# ObdBackplane.net
KiCad netlist of a schematic drawn in EAGLE
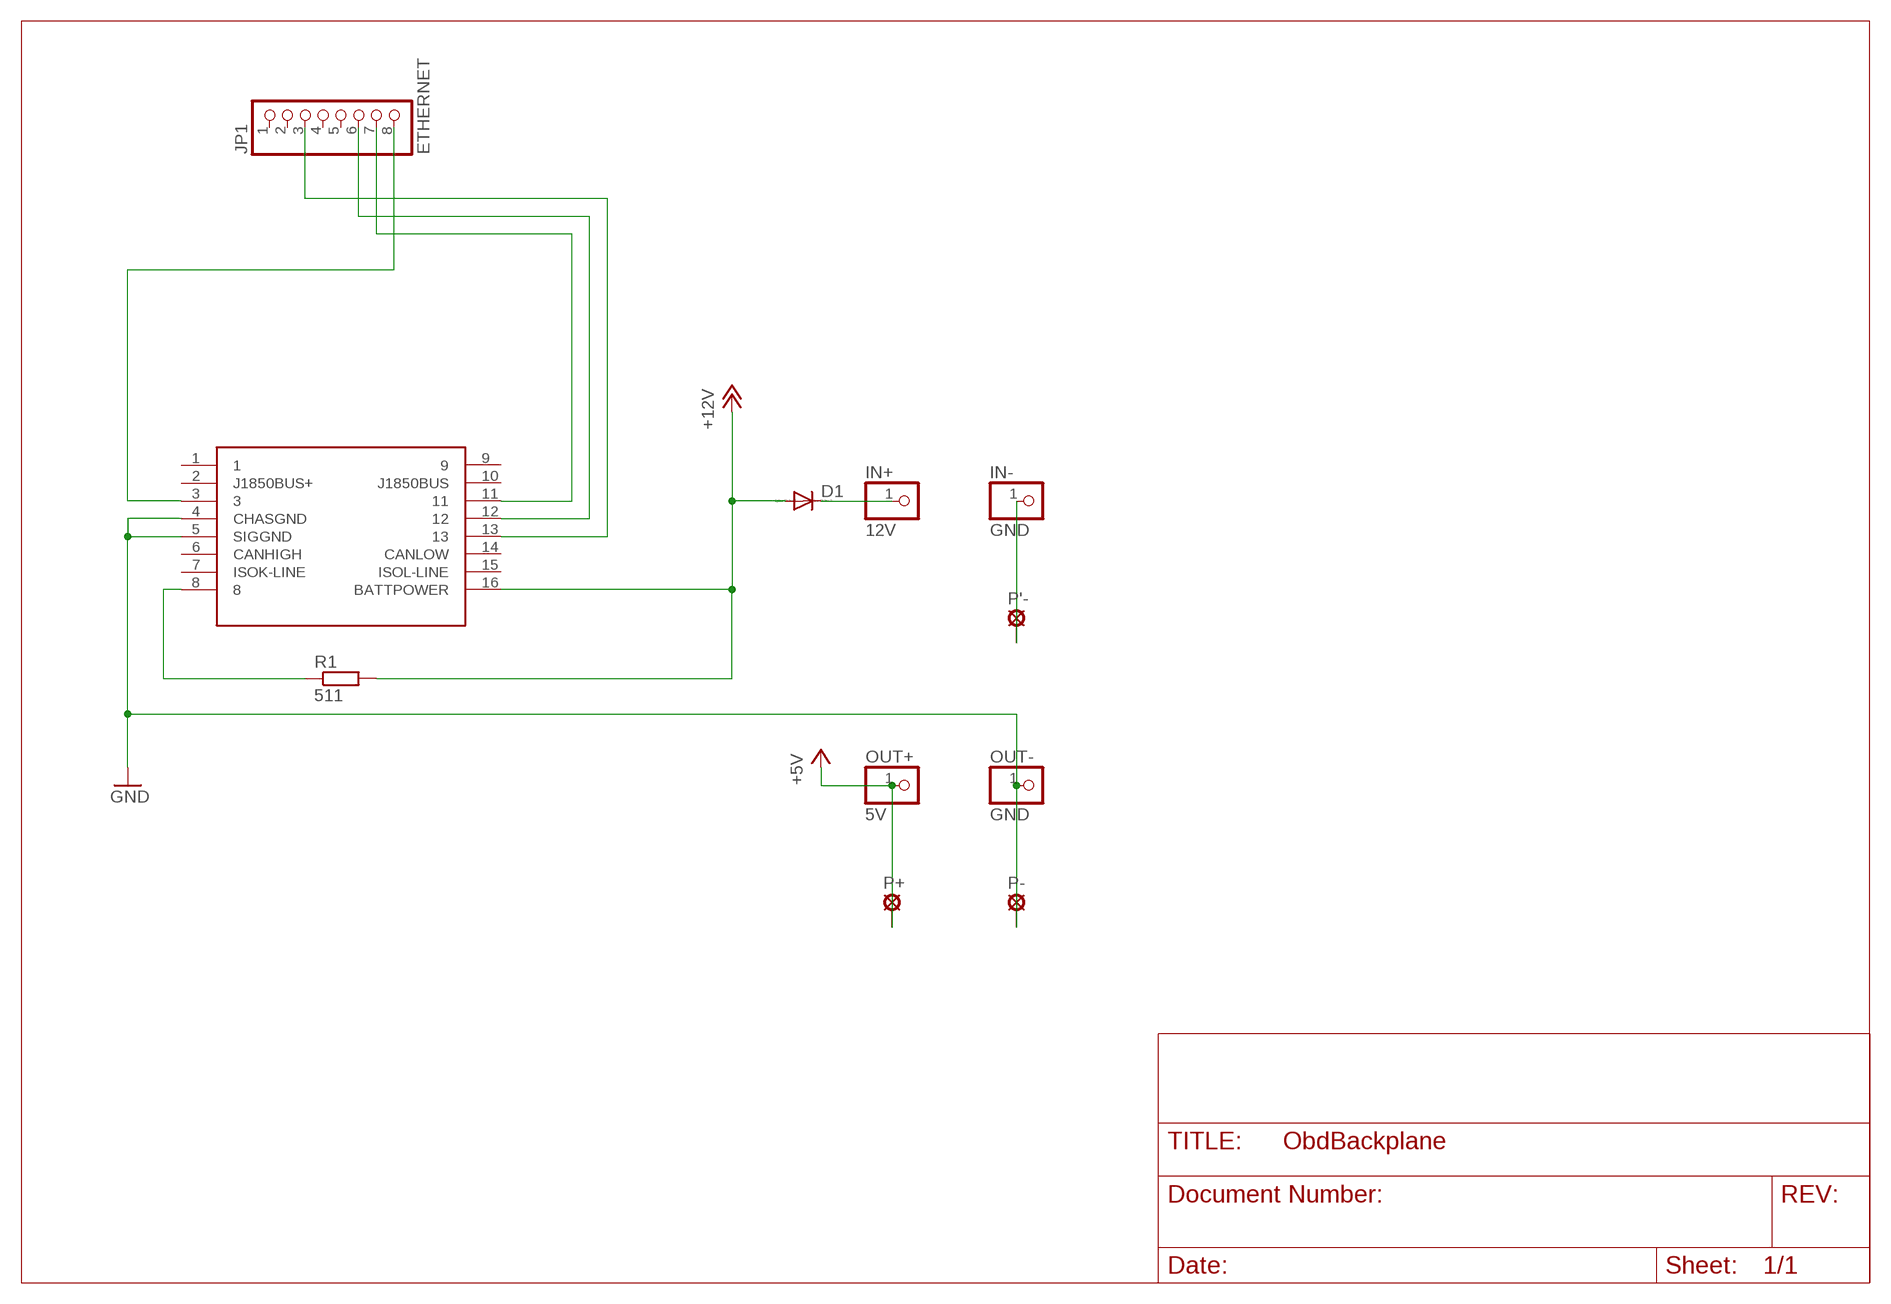
[diagram p0: schematic, sheet 1]

(export (version "E")
  (design (tool "Eeschema 10.0.6"))
  (components
    (comp (ref "D1")
      (value "DIODE-DO214AC")
      (footprint "eagle-import:DO214AC")
      (libsource (lib "eagle-import") (part "DIODE-DO214AC"))
    )
    (comp (ref "IN+")
      (value "12V")
      (footprint "eagle-import:1X01")
      (libsource (lib "eagle-import") (part "PINHD-1X1"))
    )
    (comp (ref "IN-")
      (value "GND")
      (footprint "eagle-import:1X01")
      (libsource (lib "eagle-import") (part "PINHD-1X1"))
    )
    (comp (ref "JP1")
      (value "ETHERNET")
      (footprint "eagle-import:1X08M-1MM")
      (libsource (lib "eagle-import") (part "PINHD-1X8_1.00"))
    )
    (comp (ref "OBDII")
      (value "OBDII")
      (footprint "eagle-import:OBDII")
      (libsource (lib "eagle-import") (part "OBDII"))
    )
    (comp (ref "OUT+")
      (value "5V")
      (footprint "eagle-import:1X01")
      (libsource (lib "eagle-import") (part "PINHD-1X1"))
    )
    (comp (ref "OUT-")
      (value "GND")
      (footprint "eagle-import:1X01")
      (libsource (lib "eagle-import") (part "PINHD-1X1"))
    )
    (comp (ref "P'-")
      (value "SE14")
      (footprint "eagle-import:SE14")
      (libsource (lib "eagle-import") (part "SE14"))
    )
    (comp (ref "P+")
      (value "SE14")
      (footprint "eagle-import:SE14")
      (libsource (lib "eagle-import") (part "SE14"))
    )
    (comp (ref "P-")
      (value "SE14")
      (footprint "eagle-import:SE14")
      (libsource (lib "eagle-import") (part "SE14"))
    )
    (comp (ref "R1")
      (value "511")
      (footprint "eagle-import:R2512")
      (libsource (lib "eagle-import") (part "R-EU_R2512"))
    )
  )
  (nets
    (net (code "1") (name "+5V") (class "Default")
      (node (ref "OUT+") (pin "1") (pinfunction "1_1") (pintype "passive"))
      (node (ref "P+") (pin "MP") (pinfunction "MP_MP") (pintype "passive"))
    )
    (net (code "2") (name "+12V") (class "Default")
      (node (ref "D1") (pin "A") (pinfunction "A_A") (pintype "passive"))
      (node (ref "OBDII") (pin "16") (pinfunction "BATTPOWER_16") (pintype "bidirectional"))
      (node (ref "R1") (pin "2") (pinfunction "2_2") (pintype "passive"))
    )
    (net (code "3") (name "GND") (class "Default")
      (node (ref "OBDII") (pin "4") (pinfunction "CHASGND_4") (pintype "bidirectional"))
      (node (ref "OBDII") (pin "5") (pinfunction "SIGGND_5") (pintype "bidirectional"))
      (node (ref "OUT-") (pin "1") (pinfunction "1_1") (pintype "passive"))
      (node (ref "P-") (pin "MP") (pinfunction "MP_MP") (pintype "passive"))
    )
    (net (code "4") (name "Net-(D1-PadC)") (class "Default")
      (node (ref "D1") (pin "C") (pinfunction "C_C") (pintype "passive"))
      (node (ref "IN+") (pin "1") (pinfunction "1_1") (pintype "passive"))
    )
    (net (code "5") (name "Net-(IN--Pad1)") (class "Default")
      (node (ref "IN-") (pin "1") (pinfunction "1_1") (pintype "passive"))
      (node (ref "P'-") (pin "MP") (pinfunction "MP_MP") (pintype "passive"))
    )
    (net (code "6") (name "Net-(JP1-Pad3)") (class "Default")
      (node (ref "JP1") (pin "3") (pinfunction "3_3") (pintype "passive"))
      (node (ref "OBDII") (pin "13") (pinfunction "13_13") (pintype "bidirectional"))
    )
    (net (code "7") (name "Net-(JP1-Pad6)") (class "Default")
      (node (ref "JP1") (pin "6") (pinfunction "6_6") (pintype "passive"))
      (node (ref "OBDII") (pin "12") (pinfunction "12_12") (pintype "bidirectional"))
    )
    (net (code "8") (name "Net-(JP1-Pad7)") (class "Default")
      (node (ref "JP1") (pin "7") (pinfunction "7_7") (pintype "passive"))
      (node (ref "OBDII") (pin "11") (pinfunction "11_11") (pintype "bidirectional"))
    )
    (net (code "9") (name "Net-(JP1-Pad8)") (class "Default")
      (node (ref "JP1") (pin "8") (pinfunction "8_8") (pintype "passive"))
      (node (ref "OBDII") (pin "3") (pinfunction "3_3") (pintype "bidirectional"))
    )
    (net (code "10") (name "Net-(OBDII-Pad8)") (class "Default")
      (node (ref "OBDII") (pin "8") (pinfunction "8_8") (pintype "bidirectional"))
      (node (ref "R1") (pin "1") (pinfunction "1_1") (pintype "passive"))
    )
    (net (code "11") (name "unconnected-(JP1-Pad1)") (class "Default")
      (node (ref "JP1") (pin "1") (pinfunction "1_1") (pintype "passive"))
    )
    (net (code "12") (name "unconnected-(JP1-Pad2)") (class "Default")
      (node (ref "JP1") (pin "2") (pinfunction "2_2") (pintype "passive"))
    )
    (net (code "13") (name "unconnected-(JP1-Pad4)") (class "Default")
      (node (ref "JP1") (pin "4") (pinfunction "4_4") (pintype "passive"))
    )
    (net (code "14") (name "unconnected-(JP1-Pad5)") (class "Default")
      (node (ref "JP1") (pin "5") (pinfunction "5_5") (pintype "passive"))
    )
    (net (code "15") (name "unconnected-(OBDII-CANHIGH-Pad6)") (class "Default")
      (node (ref "OBDII") (pin "6") (pinfunction "CANHIGH_6") (pintype "bidirectional"))
    )
    (net (code "16") (name "unconnected-(OBDII-CANLOW-Pad14)") (class "Default")
      (node (ref "OBDII") (pin "14") (pinfunction "CANLOW_14") (pintype "bidirectional"))
    )
    (net (code "17") (name "unconnected-(OBDII-ISOK-LINE-Pad7)") (class "Default")
      (node (ref "OBDII") (pin "7") (pinfunction "ISOK-LINE_7") (pintype "bidirectional"))
    )
    (net (code "18") (name "unconnected-(OBDII-ISOL-LINE-Pad15)") (class "Default")
      (node (ref "OBDII") (pin "15") (pinfunction "ISOL-LINE_15") (pintype "bidirectional"))
    )
    (net (code "19") (name "unconnected-(OBDII-J1850BUS+-Pad2)") (class "Default")
      (node (ref "OBDII") (pin "2") (pinfunction "J1850BUS+_2") (pintype "bidirectional"))
    )
    (net (code "20") (name "unconnected-(OBDII-J1850BUS-Pad10)") (class "Default")
      (node (ref "OBDII") (pin "10") (pinfunction "J1850BUS_10") (pintype "bidirectional"))
    )
    (net (code "21") (name "unconnected-(OBDII-Pad1)") (class "Default")
      (node (ref "OBDII") (pin "1") (pinfunction "1_1") (pintype "bidirectional"))
    )
    (net (code "22") (name "unconnected-(OBDII-Pad9)") (class "Default")
      (node (ref "OBDII") (pin "9") (pinfunction "9_9") (pintype "bidirectional"))
    )
  )
)
